# USB-FLASH.net
KiCad netlist of a schematic drawn in Altium Designer
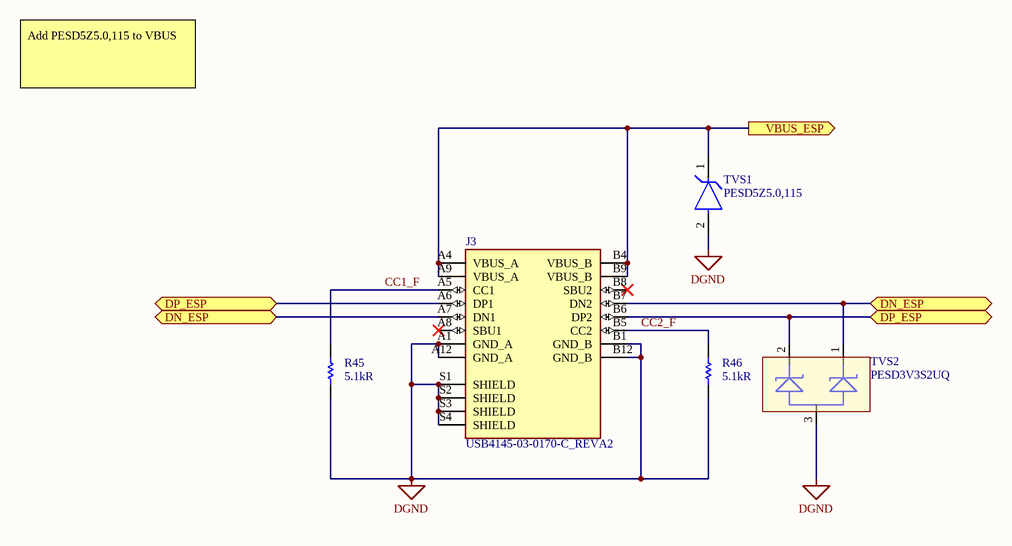
[diagram p0: USB-FLASH.SchDoc]

(export (version "E")
  (design (tool "Eeschema 10.0.6"))
  (components
    (comp (ref "J3")
      (value "USB4145-03-0170-C_REVA2")
      (footprint "GCT_USB4145-03-0170-C_REVA2")
      (libsource (lib "Digital Shovel") (part "USB4145-03-0170-C_REVA2"))
    )
    (comp (ref "R45")
      (value "5.1kR")
      (footprint "RESC1005X40X25ML10T10")
      (fields (field (name "MANUFACTURER") "KOA Speer") (field (name "PART NUMBER") "RK73H1ETTP5101F"))
      (libsource (lib "Altium Content Vault") (part "RES"))
    )
    (comp (ref "R46")
      (value "5.1kR")
      (footprint "RESC1005X40X25ML10T10")
      (fields (field (name "MANUFACTURER") "KOA Speer") (field (name "PART NUMBER") "RK73H1ETTP5101F"))
      (libsource (lib "Altium Content Vault") (part "RES"))
    )
    (comp (ref "TVS1")
      (value "PESD5Z5.0,115")
      (footprint "DIO_BAS716,115")
      (description "Trans Voltage Suppressor Diode, 180W, 5V V(RWM), Unidirectional, 1 Element, Silicon")
      (fields (field (name "MANUFACTURER") "Nexperia"))
      (libsource (lib "Digital Shovel") (part "PESD5Z5.0,115-Symbol-1"))
    )
    (comp (ref "TVS2")
      (value "PESD3V3S2UQ")
      (footprint "SOT663_NXP")
      (description "No Description Available")
      (libsource (lib "Digital Shovel") (part "PESD3V3S2UQ"))
    )
  )
  (nets
    (net (code "1") (name "/CC1_F") (class "Default")
      (node (ref "J3") (pin "A5") (pinfunction "CC1_A5") (pintype "bidirectional"))
      (node (ref "R45") (pin "2") (pinfunction "2_2") (pintype "passive"))
    )
    (net (code "2") (name "/CC2_F") (class "Default")
      (node (ref "J3") (pin "B5") (pinfunction "CC2_B5") (pintype "bidirectional"))
      (node (ref "R46") (pin "2") (pinfunction "2_2") (pintype "passive"))
    )
    (net (code "3") (name "/DN_ESP") (class "Default")
      (node (ref "J3") (pin "A7") (pinfunction "DN1_A7") (pintype "bidirectional"))
      (node (ref "J3") (pin "B7") (pinfunction "DN2_B7") (pintype "bidirectional"))
      (node (ref "TVS2") (pin "1") (pinfunction "1_1") (pintype "passive"))
    )
    (net (code "4") (name "/DP_ESP") (class "Default")
      (node (ref "J3") (pin "A6") (pinfunction "DP1_A6") (pintype "bidirectional"))
      (node (ref "J3") (pin "B6") (pinfunction "DP2_B6") (pintype "bidirectional"))
      (node (ref "TVS2") (pin "2") (pinfunction "2_2") (pintype "passive"))
    )
    (net (code "5") (name "/VBUS_ESP") (class "Default")
      (node (ref "J3") (pin "A4") (pinfunction "VBUS_A_A4") (pintype "power_in"))
      (node (ref "J3") (pin "A9") (pinfunction "VBUS_A_A9") (pintype "power_in"))
      (node (ref "J3") (pin "B4") (pinfunction "VBUS_B_B4") (pintype "power_in"))
      (node (ref "J3") (pin "B9") (pinfunction "VBUS_B_B9") (pintype "power_in"))
      (node (ref "TVS1") (pin "1") (pinfunction "1_1") (pintype "passive"))
    )
    (net (code "6") (name "DGND") (class "Default")
      (node (ref "J3") (pin "A1") (pinfunction "GND_A_A1") (pintype "power_in"))
      (node (ref "J3") (pin "A12") (pinfunction "GND_A_A12") (pintype "power_in"))
      (node (ref "J3") (pin "B1") (pinfunction "GND_B_B1") (pintype "power_in"))
      (node (ref "J3") (pin "B12") (pinfunction "GND_B_B12") (pintype "power_in"))
      (node (ref "J3") (pin "S1") (pinfunction "SHIELD_S1") (pintype "passive"))
      (node (ref "J3") (pin "S2") (pinfunction "SHIELD_S2") (pintype "passive"))
      (node (ref "J3") (pin "S3") (pinfunction "SHIELD_S3") (pintype "passive"))
      (node (ref "J3") (pin "S4") (pinfunction "SHIELD_S4") (pintype "passive"))
      (node (ref "R45") (pin "1") (pinfunction "1_1") (pintype "passive"))
      (node (ref "R46") (pin "1") (pinfunction "1_1") (pintype "passive"))
      (node (ref "TVS1") (pin "2") (pinfunction "1_2") (pintype "passive"))
      (node (ref "TVS2") (pin "3") (pinfunction "3_3") (pintype "passive"))
    )
    (net (code "7") (name "unconnected-(J3-SBU1-PadA8)") (class "Default")
      (node (ref "J3") (pin "A8") (pinfunction "SBU1_A8") (pintype "bidirectional+no_connect"))
    )
    (net (code "8") (name "unconnected-(J3-SBU2-PadB8)") (class "Default")
      (node (ref "J3") (pin "B8") (pinfunction "SBU2_B8") (pintype "bidirectional+no_connect"))
    )
  )
)
